# IS31AP2111.net
KiCad netlist of a schematic drawn in Altium Designer
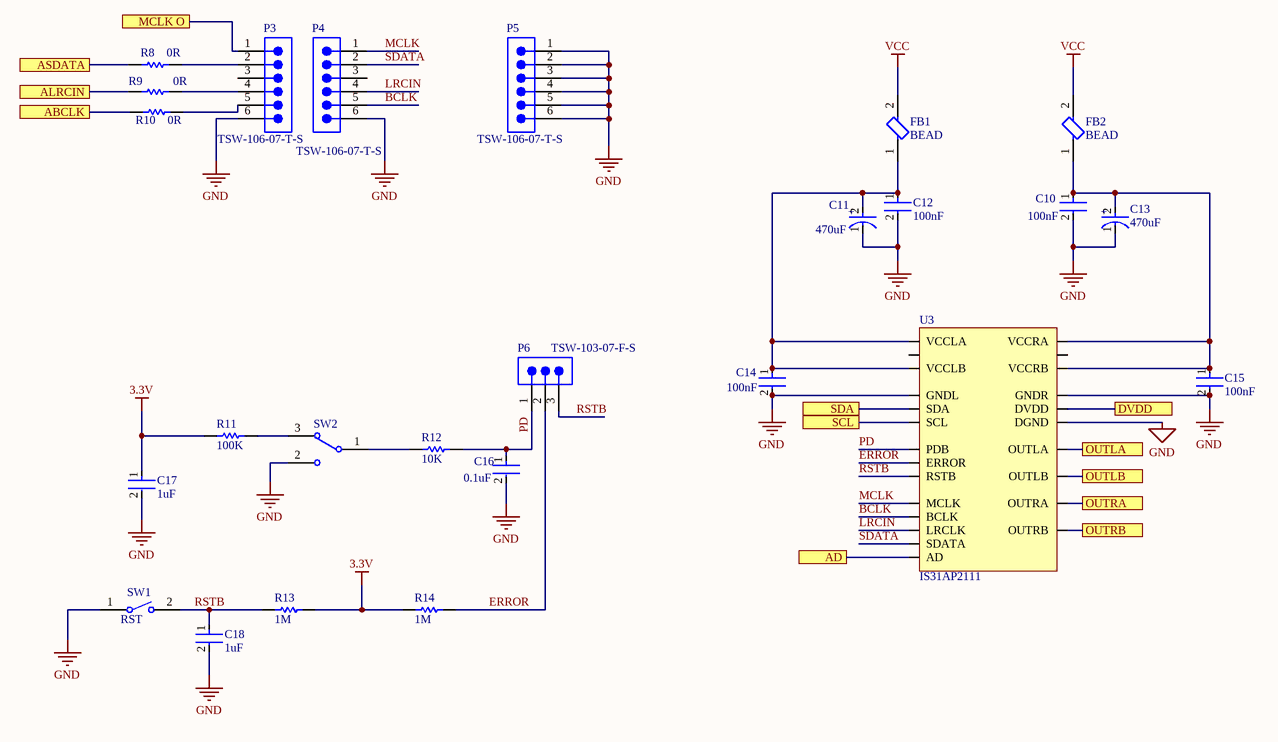
[diagram p0: IS31AP2111.SchDoc]

(export (version "E")
  (design (tool "Eeschema 10.0.6"))
  (components
    (comp (ref "C10")
      (value "100nF")
      (footprint "FP-CC0603-DA-MFG")
      (description "CAP CER 10000PF 50V X7R 0603")
      (fields (field (name "TOLERANCE") "0.1") (field (name "MANUFACTURER PART NUMBER") "CC0603KRX7R9BB103"))
      (libsource (lib "Altium Content Vault") (part "11868f565c42a9108669ba33697ecf6"))
    )
    (comp (ref "C11")
      (value "470uF")
      (footprint "FP-UUX0J471MNL1GS-MFG")
      (description "CAP ALUM 470UF 20% 6.3V SMD")
      (fields (field (name "TOLERANCE") "20%"))
      (libsource (lib "Altium Content Vault") (part "a00bbbee19879c290e62620ae7e47b1"))
    )
    (comp (ref "C12")
      (value "100nF")
      (footprint "FP-CC0603-DA-MFG")
      (description "CAP CER 10000PF 50V X7R 0603")
      (fields (field (name "TOLERANCE") "0.1") (field (name "MANUFACTURER PART NUMBER") "CC0603KRX7R9BB103"))
      (libsource (lib "Altium Content Vault") (part "11868f565c42a9108669ba33697ecf6"))
    )
    (comp (ref "C13")
      (value "470uF")
      (footprint "FP-UUX0J471MNL1GS-MFG")
      (description "CAP ALUM 470UF 20% 6.3V SMD")
      (fields (field (name "TOLERANCE") "20%"))
      (libsource (lib "Altium Content Vault") (part "a00bbbee19879c290e62620ae7e47b1"))
    )
    (comp (ref "C14")
      (value "100nF")
      (footprint "FP-CC0603-DA-MFG")
      (description "CAP CER 10000PF 50V X7R 0603")
      (fields (field (name "TOLERANCE") "0.1") (field (name "MANUFACTURER PART NUMBER") "CC0603KRX7R9BB103"))
      (libsource (lib "Altium Content Vault") (part "11868f565c42a9108669ba33697ecf6"))
    )
    (comp (ref "C15")
      (value "100nF")
      (footprint "FP-CC0603-DA-MFG")
      (description "CAP CER 10000PF 50V X7R 0603")
      (fields (field (name "TOLERANCE") "0.1") (field (name "MANUFACTURER PART NUMBER") "CC0603KRX7R9BB103"))
      (libsource (lib "Altium Content Vault") (part "11868f565c42a9108669ba33697ecf6"))
    )
    (comp (ref "C16")
      (value "0.1uF")
      (footprint "FP-CC0603-DA-MFG")
      (description "CAP CER 10000PF 50V X7R 0603")
      (fields (field (name "TOLERANCE") "0.1") (field (name "MANUFACTURER PART NUMBER") "CC0603KRX7R9BB103"))
      (libsource (lib "Altium Content Vault") (part "11868f565c42a9108669ba33697ecf6"))
    )
    (comp (ref "C17")
      (value "1uF")
      (footprint "FP-CC0603-DA-MFG")
      (description "CAP CER 10000PF 50V X7R 0603")
      (fields (field (name "TOLERANCE") "0.1") (field (name "MANUFACTURER PART NUMBER") "CC0603KRX7R9BB103"))
      (libsource (lib "Altium Content Vault") (part "11868f565c42a9108669ba33697ecf6"))
    )
    (comp (ref "C18")
      (value "1uF")
      (footprint "FP-CC0603-DA-MFG")
      (description "CAP CER 10000PF 50V X7R 0603")
      (fields (field (name "TOLERANCE") "0.1") (field (name "MANUFACTURER PART NUMBER") "CC0603KRX7R9BB103"))
      (libsource (lib "Altium Content Vault") (part "11868f565c42a9108669ba33697ecf6"))
    )
    (comp (ref "FB1")
      (value "BEAD")
      (footprint "FP-BLM18-0_15-t0_8-IPC_A")
      (description "Chip Ferrite Bead, 0603, 120Ω @ 100MHz, 0.05Ω, 25%, 2A")
      (fields (field (name "TOLERANCE") "25%"))
      (libsource (lib "Altium Content Vault") (part "5f30dd21d616792df468990f7003faa"))
    )
    (comp (ref "FB2")
      (value "BEAD")
      (footprint "FP-BLM18-0_15-t0_8-IPC_A")
      (description "Chip Ferrite Bead, 0603, 120Ω @ 100MHz, 0.05Ω, 25%, 2A")
      (fields (field (name "TOLERANCE") "25%"))
      (libsource (lib "Altium Content Vault") (part "5f30dd21d616792df468990f7003faa"))
    )
    (comp (ref "P3")
      (value "TSW-106-07-T-S")
      (footprint "SMTC-TSW-106-07-X-S")
      (description "0.025\" SQ Post Header, Through-hole, Vertical, -55 to 105 degC, 2.54 mm Pitch, 6-Pin, Male, RoHS")
      (fields (field (name "MANUFACTURER") "Samtec"))
      (libsource (lib "Altium Content Vault") (part "SMTC-TSW-106-X-X-S-X"))
    )
    (comp (ref "P4")
      (value "TSW-106-07-T-S")
      (footprint "SMTC-TSW-106-07-X-S")
      (description "0.025\" SQ Post Header, Through-hole, Vertical, -55 to 105 degC, 2.54 mm Pitch, 6-Pin, Male, RoHS")
      (fields (field (name "MANUFACTURER") "Samtec"))
      (libsource (lib "Altium Content Vault") (part "SMTC-TSW-106-X-X-S-X"))
    )
    (comp (ref "P5")
      (value "TSW-106-07-T-S")
      (footprint "SMTC-TSW-106-07-X-S")
      (description "0.025\" SQ Post Header, Through-hole, Vertical, -55 to 105 degC, 2.54 mm Pitch, 6-Pin, Male, RoHS")
      (fields (field (name "MANUFACTURER") "Samtec"))
      (libsource (lib "Altium Content Vault") (part "SMTC-TSW-106-X-X-S-X"))
    )
    (comp (ref "P6")
      (value "TSW-103-07-F-S")
      (footprint "SMTC-TSW-103-07-X-S")
      (description "0.025\" SQ Post Header, Through-hole, Vertical, -55 to 125 degC, 2.54 mm Pitch, 3-Pin, Male, RoHS")
      (fields (field (name "MANUFACTURER") "Samtec"))
      (libsource (lib "Altium Content Vault") (part "SMTC-TSW-103-X-X-S-X"))
    )
    (comp (ref "R8")
      (value "0R")
      (footprint "RESC1608X55X25ML10T15")
      (description "Chip Resistor, 100 Ohm, +/- 5%, 50 V, 0603 (1608 Metric), RoHS, Tape and Reel")
      (fields (field (name "MANUFACTURER") "Yageo") (field (name "TOLERANCE") "5%"))
      (libsource (lib "Altium Content Vault") (part "RES-2"))
    )
    (comp (ref "R9")
      (value "0R")
      (footprint "RESC1608X55X25ML10T15")
      (description "Chip Resistor, 100 Ohm, +/- 5%, 50 V, 0603 (1608 Metric), RoHS, Tape and Reel")
      (fields (field (name "MANUFACTURER") "Yageo") (field (name "TOLERANCE") "5%"))
      (libsource (lib "Altium Content Vault") (part "RES-2"))
    )
    (comp (ref "R10")
      (value "0R")
      (footprint "RESC1608X55X25ML10T15")
      (description "Chip Resistor, 100 Ohm, +/- 5%, 50 V, 0603 (1608 Metric), RoHS, Tape and Reel")
      (fields (field (name "MANUFACTURER") "Yageo") (field (name "TOLERANCE") "5%"))
      (libsource (lib "Altium Content Vault") (part "RES-2"))
    )
    (comp (ref "R11")
      (value "100K")
      (footprint "RESC1608X55X25ML10T15")
      (description "Chip Resistor, 100 Ohm, +/- 5%, 50 V, 0603 (1608 Metric), RoHS, Tape and Reel")
      (fields (field (name "MANUFACTURER") "Yageo") (field (name "TOLERANCE") "5%"))
      (libsource (lib "Altium Content Vault") (part "RES-2"))
    )
    (comp (ref "R12")
      (value "10K")
      (footprint "RESC1608X55X25ML10T15")
      (description "Chip Resistor, 100 Ohm, +/- 5%, 50 V, 0603 (1608 Metric), RoHS, Tape and Reel")
      (fields (field (name "MANUFACTURER") "Yageo") (field (name "TOLERANCE") "5%"))
      (libsource (lib "Altium Content Vault") (part "RES-2"))
    )
    (comp (ref "R13")
      (value "1M")
      (footprint "RESC1608X55X25LL10T15")
      (fields (field (name "MANUFACTURER") "Yageo"))
      (libsource (lib "Altium Content Vault") (part "RES-2"))
    )
    (comp (ref "R14")
      (value "1M")
      (footprint "RESC1608X55X25LL10T15")
      (fields (field (name "MANUFACTURER") "Yageo"))
      (libsource (lib "Altium Content Vault") (part "RES-2"))
    )
    (comp (ref "SW1")
      (value "RST")
      (footprint "TECO-FSMSM-2_V")
      (description "FSMSM Push Button Switch, 50 mA, -35 to 85 degC, 2-Pin SMD, RoHS, Bulk")
      (fields (field (name "MANUFACTURER") "TE Connectivity"))
      (libsource (lib "Altium Content Vault") (part "SW-SPST-2_C"))
    )
    (comp (ref "SW2")
      (value "450301014042")
      (footprint "450301014042")
      (description "WS-SLTV 10mm*2.5mm, SPDT, ON-ON, 2.54mm, straight type, THT, Mini Slide Switch, 3 pins")
      (fields (field (name "MANUFACTURER") "Wuerth Elektronik"))
      (libsource (lib "Altium Content Vault") (part "WE-SLIDE-SW-3"))
    )
    (comp (ref "U3")
      (value "IS31AP2111")
      (footprint "pcb-libs:eTSSOP-24")
      (description "2x20W STEREO/1x40W MONO DIGITAL (I2S) AUDIO AMPLIFIER WITH 20 BANDS EQ FUNCTIONS")
      (libsource (lib "sch-libs") (part "IS31AP2111_Trotta"))
    )
  )
  (nets
    (net (code "1") (name "/ABCLK") (class "Default")
      (node (ref "R10") (pin "1") (pinfunction "1_1") (pintype "passive"))
    )
    (net (code "2") (name "/AD") (class "Default")
      (node (ref "U3") (pin "10") (pinfunction "AD_10") (pintype "passive"))
    )
    (net (code "3") (name "/ALRCIN") (class "Default")
      (node (ref "R9") (pin "1") (pinfunction "1_1") (pintype "passive"))
    )
    (net (code "4") (name "/ASDATA") (class "Default")
      (node (ref "R8") (pin "1") (pinfunction "1_1") (pintype "passive"))
    )
    (net (code "5") (name "/BCLK") (class "Default")
      (node (ref "P4") (pin "5") (pinfunction "5_5") (pintype "passive"))
      (node (ref "U3") (pin "12") (pinfunction "BCLK_12") (pintype "passive"))
    )
    (net (code "6") (name "/DVDD") (class "Default")
      (node (ref "U3") (pin "9") (pinfunction "DVDD_9") (pintype "passive"))
    )
    (net (code "7") (name "/ERROR") (class "Default")
      (node (ref "P6") (pin "2") (pinfunction "2_2") (pintype "passive"))
      (node (ref "R14") (pin "2") (pinfunction "2_2") (pintype "passive"))
      (node (ref "U3") (pin "2") (pinfunction "ERROR_2") (pintype "passive"))
    )
    (net (code "8") (name "/LRCIN") (class "Default")
      (node (ref "P4") (pin "4") (pinfunction "4_4") (pintype "passive"))
      (node (ref "U3") (pin "4") (pinfunction "LRCLK_4") (pintype "passive"))
    )
    (net (code "9") (name "/MCLK") (class "Default")
      (node (ref "P4") (pin "1") (pinfunction "1_1") (pintype "passive"))
      (node (ref "U3") (pin "11") (pinfunction "MCLK_11") (pintype "passive"))
    )
    (net (code "10") (name "/MCLK O") (class "Default")
      (node (ref "P3") (pin "1") (pinfunction "1_1") (pintype "passive"))
    )
    (net (code "11") (name "/OUTLA") (class "Default")
      (node (ref "U3") (pin "22") (pinfunction "OUTLA_22") (pintype "passive"))
    )
    (net (code "12") (name "/OUTLB") (class "Default")
      (node (ref "U3") (pin "20") (pinfunction "OUTLB_20") (pintype "passive"))
    )
    (net (code "13") (name "/OUTRA") (class "Default")
      (node (ref "U3") (pin "15") (pinfunction "OUTRA_15") (pintype "passive"))
    )
    (net (code "14") (name "/OUTRB") (class "Default")
      (node (ref "U3") (pin "17") (pinfunction "OUTRB_17") (pintype "passive"))
    )
    (net (code "15") (name "/PD") (class "Default")
      (node (ref "C16") (pin "1") (pinfunction "1_1") (pintype "passive"))
      (node (ref "P6") (pin "1") (pinfunction "1_1") (pintype "passive"))
      (node (ref "R12") (pin "2") (pinfunction "2_2") (pintype "passive"))
      (node (ref "U3") (pin "1") (pinfunction "PDB_1") (pintype "passive"))
    )
    (net (code "16") (name "/RSTB") (class "Default")
      (node (ref "C18") (pin "1") (pinfunction "1_1") (pintype "passive"))
      (node (ref "P6") (pin "3") (pinfunction "3_3") (pintype "passive"))
      (node (ref "R13") (pin "1") (pinfunction "1_1") (pintype "passive"))
      (node (ref "SW1") (pin "2") (pinfunction "2_2") (pintype "passive"))
      (node (ref "U3") (pin "7") (pinfunction "RSTB_7") (pintype "passive"))
    )
    (net (code "17") (name "/SCL") (class "Default")
      (node (ref "U3") (pin "6") (pinfunction "SCL_6") (pintype "passive"))
    )
    (net (code "18") (name "/SDA") (class "Default")
      (node (ref "U3") (pin "5") (pinfunction "SDA_5") (pintype "passive"))
    )
    (net (code "19") (name "/SDATA") (class "Default")
      (node (ref "P4") (pin "2") (pinfunction "2_2") (pintype "passive"))
      (node (ref "U3") (pin "3") (pinfunction "SDATA_3") (pintype "passive"))
    )
    (net (code "20") (name "3.3V") (class "Default")
      (node (ref "C17") (pin "1") (pinfunction "1_1") (pintype "passive"))
      (node (ref "R11") (pin "1") (pinfunction "1_1") (pintype "passive"))
      (node (ref "R13") (pin "2") (pinfunction "2_2") (pintype "passive"))
      (node (ref "R14") (pin "1") (pinfunction "1_1") (pintype "passive"))
    )
    (net (code "21") (name "GND") (class "Default")
      (node (ref "C10") (pin "2") (pinfunction "2_2") (pintype "passive"))
      (node (ref "C11") (pin "1") (pinfunction "C_1") (pintype "passive"))
      (node (ref "C12") (pin "2") (pinfunction "2_2") (pintype "passive"))
      (node (ref "C13") (pin "1") (pinfunction "C_1") (pintype "passive"))
      (node (ref "C14") (pin "2") (pinfunction "2_2") (pintype "passive"))
      (node (ref "C15") (pin "2") (pinfunction "2_2") (pintype "passive"))
      (node (ref "C16") (pin "2") (pinfunction "2_2") (pintype "passive"))
      (node (ref "C17") (pin "2") (pinfunction "2_2") (pintype "passive"))
      (node (ref "C18") (pin "2") (pinfunction "2_2") (pintype "passive"))
      (node (ref "P3") (pin "6") (pinfunction "6_6") (pintype "passive"))
      (node (ref "P4") (pin "6") (pinfunction "6_6") (pintype "passive"))
      (node (ref "P5") (pin "1") (pinfunction "1_1") (pintype "passive"))
      (node (ref "P5") (pin "2") (pinfunction "2_2") (pintype "passive"))
      (node (ref "P5") (pin "3") (pinfunction "3_3") (pintype "passive"))
      (node (ref "P5") (pin "4") (pinfunction "4_4") (pintype "passive"))
      (node (ref "P5") (pin "5") (pinfunction "5_5") (pintype "passive"))
      (node (ref "P5") (pin "6") (pinfunction "6_6") (pintype "passive"))
      (node (ref "SW1") (pin "1") (pinfunction "1_1") (pintype "passive"))
      (node (ref "SW2") (pin "2") (pinfunction "2_2") (pintype "passive"))
      (node (ref "U3") (pin "16") (pinfunction "GNDR_16") (pintype "passive"))
      (node (ref "U3") (pin "21") (pinfunction "GNDL_21") (pintype "passive"))
      (node (ref "U3") (pin "8") (pinfunction "DGND_8") (pintype "passive"))
    )
    (net (code "22") (name "Net-(C11-A)") (class "Default")
      (node (ref "C11") (pin "2") (pinfunction "A_2") (pintype "passive"))
      (node (ref "C12") (pin "1") (pinfunction "1_1") (pintype "passive"))
      (node (ref "C14") (pin "1") (pinfunction "1_1") (pintype "passive"))
      (node (ref "FB1") (pin "1") (pinfunction "1_1") (pintype "passive"))
      (node (ref "U3") (pin "19") (pinfunction "VCCLB_19") (pintype "passive"))
      (node (ref "U3") (pin "24") (pinfunction "VCCLA_24") (pintype "passive"))
    )
    (net (code "23") (name "Net-(C13-A)") (class "Default")
      (node (ref "C10") (pin "1") (pinfunction "1_1") (pintype "passive"))
      (node (ref "C13") (pin "2") (pinfunction "A_2") (pintype "passive"))
      (node (ref "C15") (pin "1") (pinfunction "1_1") (pintype "passive"))
      (node (ref "FB2") (pin "1") (pinfunction "1_1") (pintype "passive"))
      (node (ref "U3") (pin "13") (pinfunction "VCCRA_13") (pintype "passive"))
      (node (ref "U3") (pin "18") (pinfunction "VCCRB_18") (pintype "passive"))
    )
    (net (code "24") (name "Net-(P3-Pad2)") (class "Default")
      (node (ref "P3") (pin "2") (pinfunction "2_2") (pintype "passive"))
      (node (ref "R8") (pin "2") (pinfunction "2_2") (pintype "passive"))
    )
    (net (code "25") (name "Net-(P3-Pad4)") (class "Default")
      (node (ref "P3") (pin "4") (pinfunction "4_4") (pintype "passive"))
      (node (ref "R9") (pin "2") (pinfunction "2_2") (pintype "passive"))
    )
    (net (code "26") (name "Net-(P3-Pad5)") (class "Default")
      (node (ref "P3") (pin "5") (pinfunction "5_5") (pintype "passive"))
      (node (ref "R10") (pin "2") (pinfunction "2_2") (pintype "passive"))
    )
    (net (code "27") (name "Net-(R11-Pad2)") (class "Default")
      (node (ref "R11") (pin "2") (pinfunction "2_2") (pintype "passive"))
      (node (ref "SW2") (pin "3") (pinfunction "3_3") (pintype "passive"))
    )
    (net (code "28") (name "Net-(R12-Pad1)") (class "Default")
      (node (ref "R12") (pin "1") (pinfunction "1_1") (pintype "passive"))
      (node (ref "SW2") (pin "1") (pinfunction "1_1") (pintype "passive"))
    )
    (net (code "29") (name "VCC") (class "Default")
      (node (ref "FB1") (pin "2") (pinfunction "2_2") (pintype "passive"))
      (node (ref "FB2") (pin "2") (pinfunction "2_2") (pintype "passive"))
    )
    (net (code "30") (name "unconnected-(P3-Pad3)") (class "Default")
      (node (ref "P3") (pin "3") (pinfunction "3_3") (pintype "passive"))
    )
    (net (code "31") (name "unconnected-(P4-Pad3)") (class "Default")
      (node (ref "P4") (pin "3") (pinfunction "3_3") (pintype "passive"))
    )
    (net (code "32") (name "unconnected-(U3-Pad14)") (class "Default")
      (node (ref "U3") (pin "14") (pintype "passive"))
    )
    (net (code "33") (name "unconnected-(U3-Pad23)") (class "Default")
      (node (ref "U3") (pin "23") (pintype "passive"))
    )
  )
)
